# acoustic_1_0.net
KiCad netlist of a schematic drawn in EAGLE
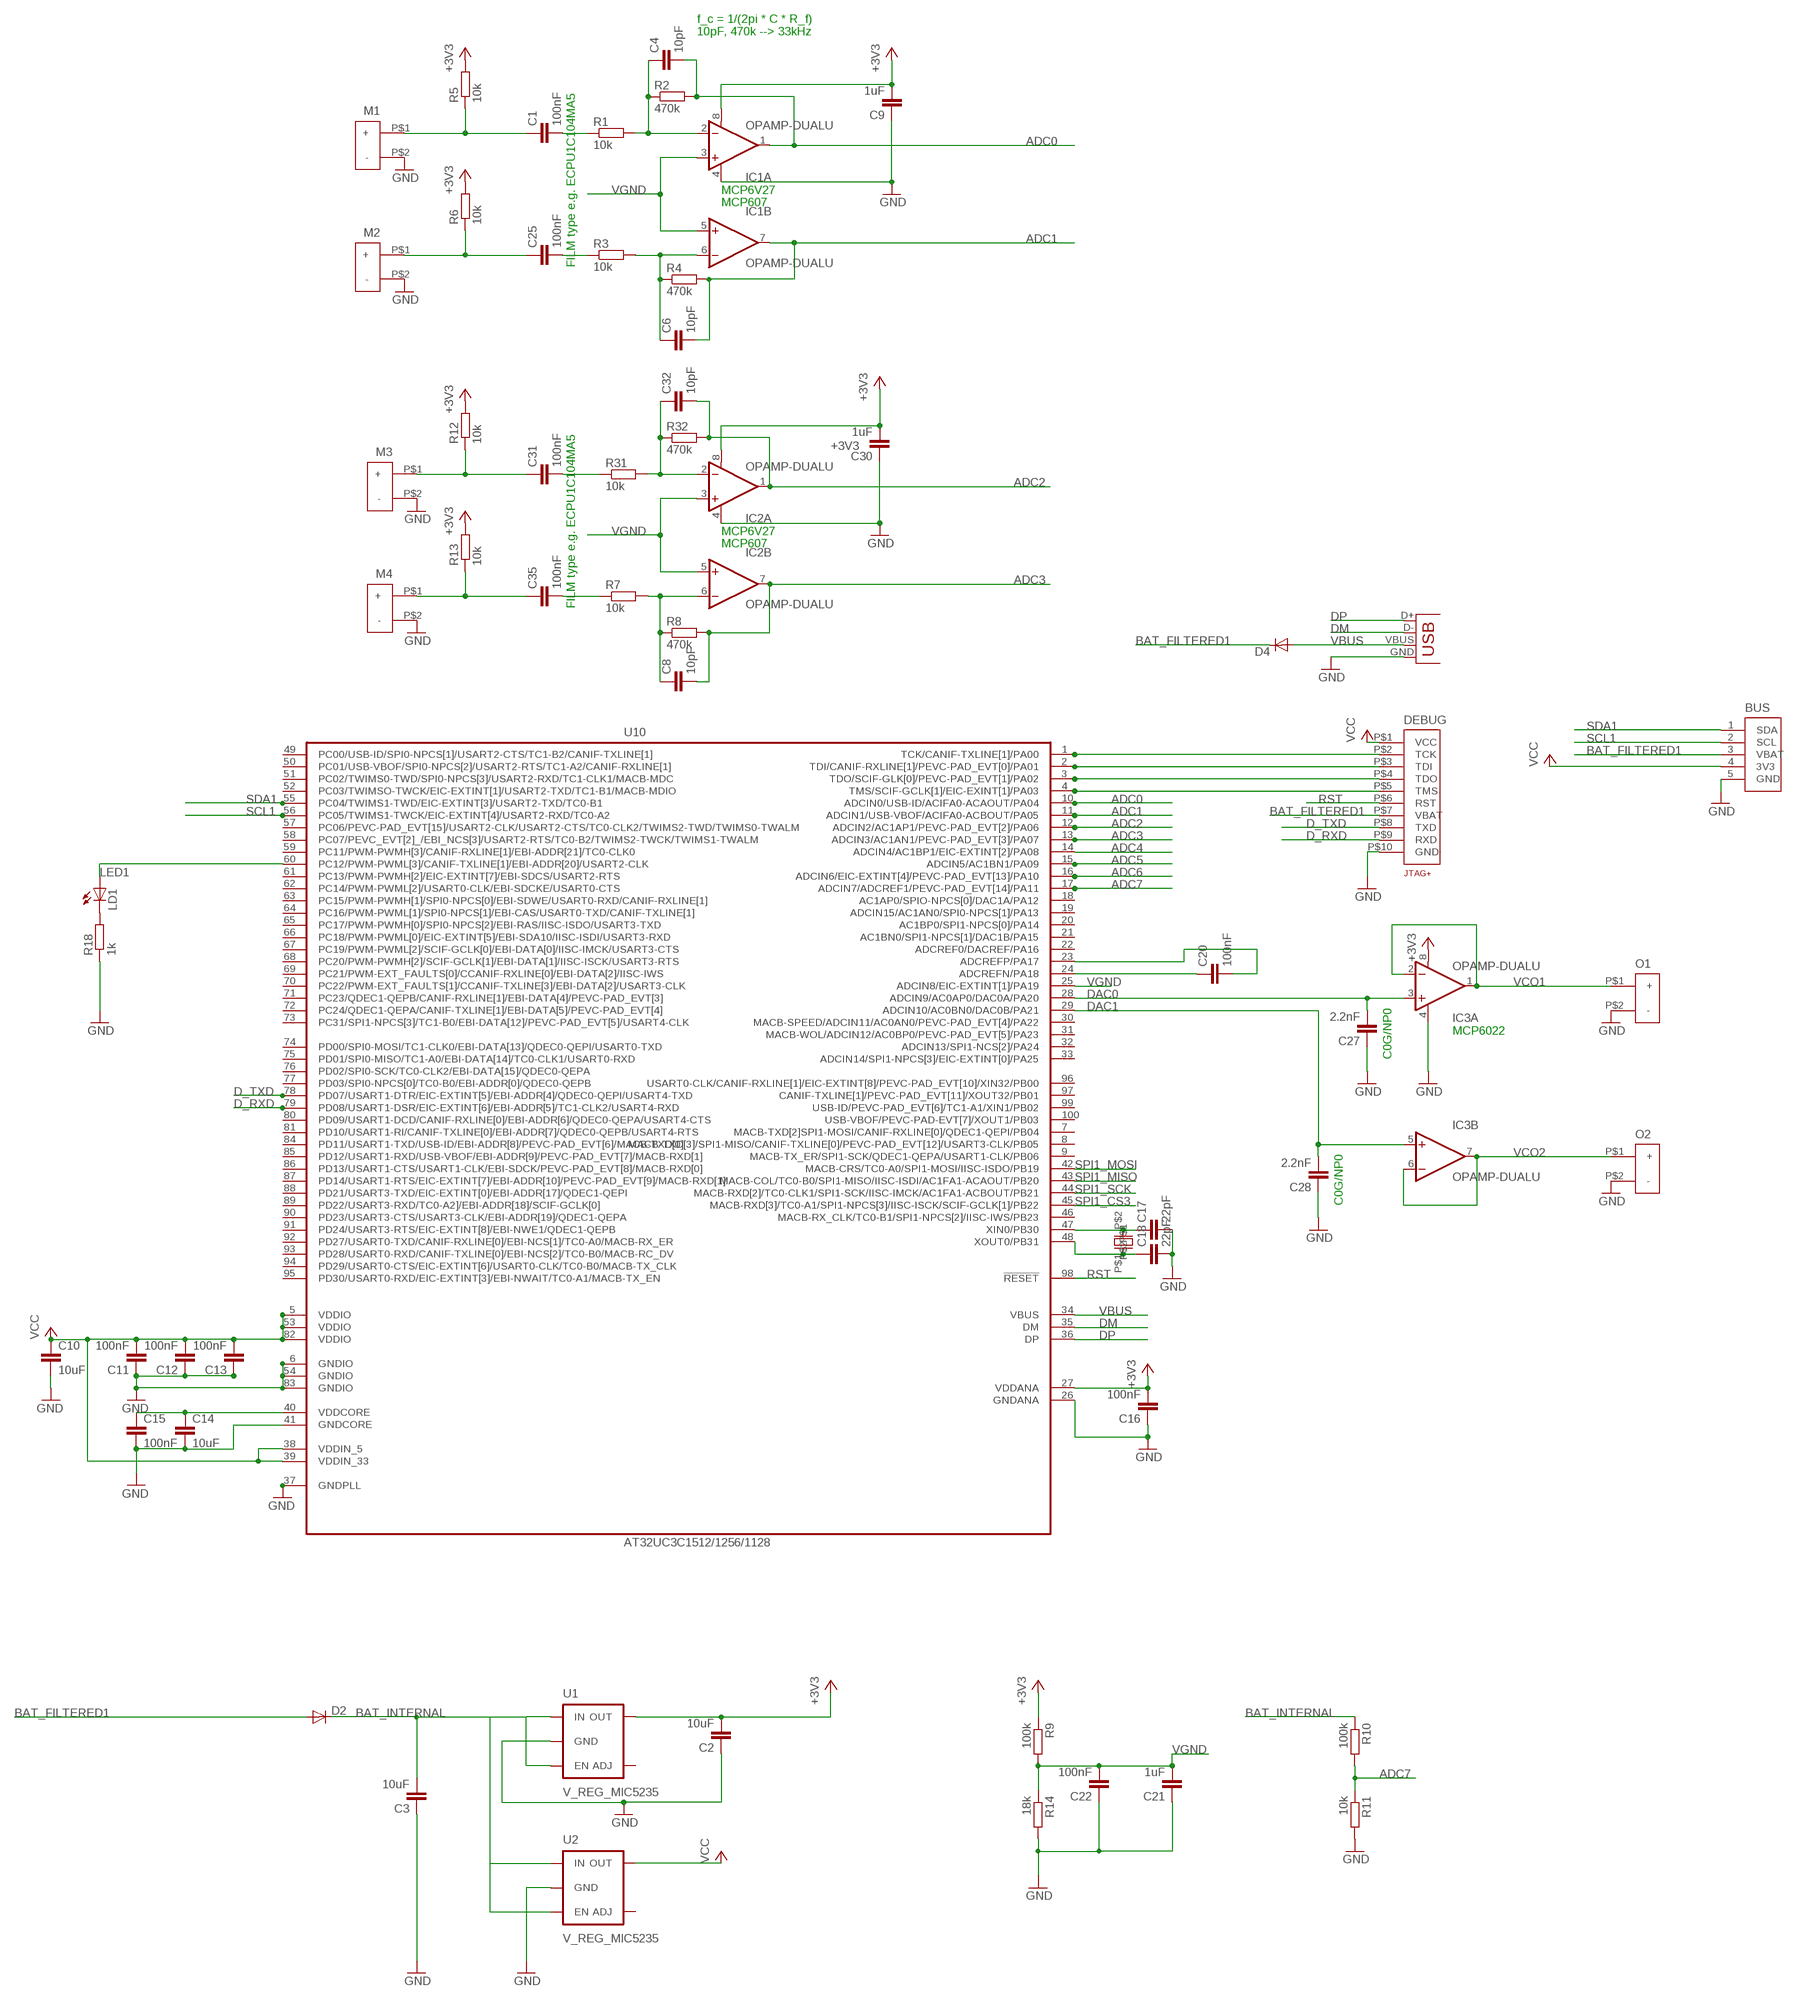
[diagram p0: schematic, sheet 1]

(export (version "E")
  (design (tool "Eeschema 10.0.6"))
  (components
    (comp (ref "BUS")
      (value "I2C_BUS_PICOVERTICAL")
      (footprint "eagle-import:MOLEX_CONNECTOR_5_PINS_VERTICAL")
      (fields (field (name "PLACE_PART") "YES"))
      (libsource (lib "eagle-import") (part "I2C_BUS_PICOVERTICAL"))
    )
    (comp (ref "C1")
      (value "100nF")
      (footprint "eagle-import:C0805")
      (libsource (lib "eagle-import") (part "C-EUC0805"))
    )
    (comp (ref "C2")
      (value "10uF")
      (footprint "eagle-import:C0805")
      (libsource (lib "eagle-import") (part "C-EUC0805"))
    )
    (comp (ref "C3")
      (value "10uF")
      (footprint "eagle-import:C0805")
      (libsource (lib "eagle-import") (part "C-EUC0805"))
    )
    (comp (ref "C4")
      (value "10pF")
      (footprint "eagle-import:C0603")
      (libsource (lib "eagle-import") (part "C-EUC0603"))
    )
    (comp (ref "C6")
      (value "10pF")
      (footprint "eagle-import:C0603")
      (libsource (lib "eagle-import") (part "C-EUC0603"))
    )
    (comp (ref "C8")
      (value "10pF")
      (footprint "eagle-import:C0603")
      (libsource (lib "eagle-import") (part "C-EUC0603"))
    )
    (comp (ref "C9")
      (value "1uF")
      (footprint "eagle-import:C0805")
      (libsource (lib "eagle-import") (part "C-EUC0805"))
    )
    (comp (ref "C10")
      (value "10uF")
      (footprint "eagle-import:C0805")
      (libsource (lib "eagle-import") (part "C-EUC0805"))
    )
    (comp (ref "C11")
      (value "100nF")
      (footprint "eagle-import:C0603")
      (libsource (lib "eagle-import") (part "C-EUC0603"))
    )
    (comp (ref "C12")
      (value "100nF")
      (footprint "eagle-import:C0603")
      (libsource (lib "eagle-import") (part "C-EUC0603"))
    )
    (comp (ref "C13")
      (value "100nF")
      (footprint "eagle-import:C0603")
      (libsource (lib "eagle-import") (part "C-EUC0603"))
    )
    (comp (ref "C14")
      (value "10uF")
      (footprint "eagle-import:C0805")
      (libsource (lib "eagle-import") (part "C-EUC0805"))
    )
    (comp (ref "C15")
      (value "100nF")
      (footprint "eagle-import:C0603")
      (libsource (lib "eagle-import") (part "C-EUC0603"))
    )
    (comp (ref "C16")
      (value "100nF")
      (footprint "eagle-import:C0603")
      (libsource (lib "eagle-import") (part "C-EUC0603"))
    )
    (comp (ref "C17")
      (value "22pF")
      (footprint "eagle-import:C0402")
      (libsource (lib "eagle-import") (part "C-EUC0402"))
    )
    (comp (ref "C18")
      (value "22pF")
      (footprint "eagle-import:C0402")
      (libsource (lib "eagle-import") (part "C-EUC0402"))
    )
    (comp (ref "C20")
      (value "100nF")
      (footprint "eagle-import:C0603")
      (libsource (lib "eagle-import") (part "C-EUC0603"))
    )
    (comp (ref "C21")
      (value "1uF")
      (footprint "eagle-import:C0805")
      (libsource (lib "eagle-import") (part "C-EUC0805"))
    )
    (comp (ref "C22")
      (value "100nF")
      (footprint "eagle-import:C0603")
      (libsource (lib "eagle-import") (part "C-EUC0603"))
    )
    (comp (ref "C25")
      (value "100nF")
      (footprint "eagle-import:C0805")
      (libsource (lib "eagle-import") (part "C-EUC0805"))
    )
    (comp (ref "C27")
      (value "2.2nF")
      (footprint "eagle-import:C0805")
      (libsource (lib "eagle-import") (part "C-EUC0805"))
    )
    (comp (ref "C28")
      (value "2.2nF")
      (footprint "eagle-import:C0805")
      (libsource (lib "eagle-import") (part "C-EUC0805"))
    )
    (comp (ref "C30")
      (value "1uF")
      (footprint "eagle-import:C0805")
      (libsource (lib "eagle-import") (part "C-EUC0805"))
    )
    (comp (ref "C31")
      (value "100nF")
      (footprint "eagle-import:C0805")
      (libsource (lib "eagle-import") (part "C-EUC0805"))
    )
    (comp (ref "C32")
      (value "10pF")
      (footprint "eagle-import:C0603")
      (libsource (lib "eagle-import") (part "C-EUC0603"))
    )
    (comp (ref "C35")
      (value "100nF")
      (footprint "eagle-import:C0805")
      (libsource (lib "eagle-import") (part "C-EUC0805"))
    )
    (comp (ref "D2")
      (value "DIODESOD")
      (footprint "eagle-import:SOD-323")
      (libsource (lib "eagle-import") (part "DIODESOD"))
    )
    (comp (ref "D4")
      (value "DIODESOD")
      (footprint "eagle-import:SOD-323")
      (libsource (lib "eagle-import") (part "DIODESOD"))
    )
    (comp (ref "DEBUG")
      (value "AVR32_JTAG+SERIALHIROSE_DF13")
      (footprint "eagle-import:MOLEX_CONNECTOR_10PINS")
      (fields (field (name "PLACE_PART") "YES"))
      (libsource (lib "eagle-import") (part "AVR32_JTAG+SERIALHIROSE_DF13"))
    )
    (comp (ref "IC1")
      (value "OPAMP-DUALU")
      (footprint "eagle-import:SO08")
      (libsource (lib "eagle-import") (part "OPAMP-DUALU"))
    )
    (comp (ref "IC2")
      (value "OPAMP-DUALU")
      (footprint "eagle-import:SO08")
      (libsource (lib "eagle-import") (part "OPAMP-DUALU"))
    )
    (comp (ref "IC3")
      (value "OPAMP-DUALU")
      (footprint "eagle-import:SO08")
      (libsource (lib "eagle-import") (part "OPAMP-DUALU"))
    )
    (comp (ref "LD1")
      (value "LEDCHIPLED_0805")
      (footprint "eagle-import:CHIPLED_0805")
      (libsource (lib "eagle-import") (part "LEDCHIPLED_0805"))
    )
    (comp (ref "M1")
      (value "POWER")
      (footprint "eagle-import:POWER")
      (fields (field (name "PLACE_PART") "YES"))
      (libsource (lib "eagle-import") (part "POWER"))
    )
    (comp (ref "M2")
      (value "POWER")
      (footprint "eagle-import:POWER")
      (fields (field (name "PLACE_PART") "YES"))
      (libsource (lib "eagle-import") (part "POWER"))
    )
    (comp (ref "M3")
      (value "POWER")
      (footprint "eagle-import:POWER")
      (fields (field (name "PLACE_PART") "YES"))
      (libsource (lib "eagle-import") (part "POWER"))
    )
    (comp (ref "M4")
      (value "POWER")
      (footprint "eagle-import:POWER")
      (fields (field (name "PLACE_PART") "YES"))
      (libsource (lib "eagle-import") (part "POWER"))
    )
    (comp (ref "O1")
      (value "POWER")
      (footprint "eagle-import:POWER")
      (fields (field (name "PLACE_PART") "YES"))
      (libsource (lib "eagle-import") (part "POWER"))
    )
    (comp (ref "O2")
      (value "POWER")
      (footprint "eagle-import:POWER")
      (fields (field (name "PLACE_PART") "YES"))
      (libsource (lib "eagle-import") (part "POWER"))
    )
    (comp (ref "R1")
      (value "10k")
      (footprint "eagle-import:R0603")
      (libsource (lib "eagle-import") (part "R-EU_R0603"))
    )
    (comp (ref "R2")
      (value "470k")
      (footprint "eagle-import:R0603")
      (libsource (lib "eagle-import") (part "R-EU_R0603"))
    )
    (comp (ref "R3")
      (value "10k")
      (footprint "eagle-import:R0603")
      (libsource (lib "eagle-import") (part "R-EU_R0603"))
    )
    (comp (ref "R4")
      (value "470k")
      (footprint "eagle-import:R0603")
      (libsource (lib "eagle-import") (part "R-EU_R0603"))
    )
    (comp (ref "R5")
      (value "10k")
      (footprint "eagle-import:R0603")
      (libsource (lib "eagle-import") (part "R-EU_R0603"))
    )
    (comp (ref "R6")
      (value "10k")
      (footprint "eagle-import:R0603")
      (libsource (lib "eagle-import") (part "R-EU_R0603"))
    )
    (comp (ref "R7")
      (value "10k")
      (footprint "eagle-import:R0603")
      (libsource (lib "eagle-import") (part "R-EU_R0603"))
    )
    (comp (ref "R8")
      (value "470k")
      (footprint "eagle-import:R0603")
      (libsource (lib "eagle-import") (part "R-EU_R0603"))
    )
    (comp (ref "R9")
      (value "100k")
      (footprint "eagle-import:R0603")
      (libsource (lib "eagle-import") (part "R-EU_R0603"))
    )
    (comp (ref "R10")
      (value "100k")
      (footprint "eagle-import:R0603")
      (libsource (lib "eagle-import") (part "R-EU_R0603"))
    )
    (comp (ref "R11")
      (value "10k")
      (footprint "eagle-import:R0603")
      (libsource (lib "eagle-import") (part "R-EU_R0603"))
    )
    (comp (ref "R12")
      (value "10k")
      (footprint "eagle-import:R0603")
      (libsource (lib "eagle-import") (part "R-EU_R0603"))
    )
    (comp (ref "R13")
      (value "10k")
      (footprint "eagle-import:R0603")
      (libsource (lib "eagle-import") (part "R-EU_R0603"))
    )
    (comp (ref "R14")
      (value "18k")
      (footprint "eagle-import:R0603")
      (libsource (lib "eagle-import") (part "R-EU_R0603"))
    )
    (comp (ref "R18")
      (value "1k")
      (footprint "eagle-import:R0603")
      (libsource (lib "eagle-import") (part "R-EU_R0603"))
    )
    (comp (ref "R31")
      (value "10k")
      (footprint "eagle-import:R0603")
      (libsource (lib "eagle-import") (part "R-EU_R0603"))
    )
    (comp (ref "R32")
      (value "470k")
      (footprint "eagle-import:R0603")
      (libsource (lib "eagle-import") (part "R-EU_R0603"))
    )
    (comp (ref "U$8")
      (value "CRYSTAL")
      (footprint "eagle-import:SMD_CRYSTAL_ABM")
      (fields (field (name "PLACE_PART") "YES"))
      (libsource (lib "eagle-import") (part "CRYSTAL"))
    )
    (comp (ref "U1")
      (value "V_REG_MIC5235")
      (footprint "eagle-import:SOT23-5")
      (libsource (lib "eagle-import") (part "V_REG_MIC5235"))
    )
    (comp (ref "U2")
      (value "V_REG_MIC5235")
      (footprint "eagle-import:SOT23-5")
      (libsource (lib "eagle-import") (part "V_REG_MIC5235"))
    )
    (comp (ref "U10")
      (value "AT32UC3C1512/1256/1128")
      (footprint "eagle-import:TQFP100")
      (fields (field (name "PLACE_PART") "YES"))
      (libsource (lib "eagle-import") (part "AT32UC3C1512/1256/1128"))
    )
    (comp (ref "X1")
      (value "USB-MICROB")
      (footprint "eagle-import:USB-MICROB")
      (libsource (lib "eagle-import") (part "USB-MICROB"))
    )
  )
  (nets
    (net (code "1") (name "+3V3") (class "Default")
      (node (ref "C16") (pin "2") (pinfunction "2_2") (pintype "passive"))
      (node (ref "C2") (pin "2") (pinfunction "2_2") (pintype "passive"))
      (node (ref "C30") (pin "2") (pinfunction "2_2") (pintype "passive"))
      (node (ref "C9") (pin "2") (pinfunction "2_2") (pintype "passive"))
      (node (ref "IC1") (pin "8") (pinfunction "V+_8") (pintype "power_in"))
      (node (ref "IC2") (pin "8") (pinfunction "V+_8") (pintype "power_in"))
      (node (ref "IC3") (pin "8") (pinfunction "V+_8") (pintype "power_in"))
      (node (ref "R12") (pin "2") (pinfunction "2_2") (pintype "passive"))
      (node (ref "R13") (pin "2") (pinfunction "2_2") (pintype "passive"))
      (node (ref "R5") (pin "2") (pinfunction "2_2") (pintype "passive"))
      (node (ref "R6") (pin "2") (pinfunction "2_2") (pintype "passive"))
      (node (ref "R9") (pin "1") (pinfunction "1_1") (pintype "passive"))
      (node (ref "U1") (pin "5") (pinfunction "OUT_5") (pintype "passive"))
      (node (ref "U10") (pin "27") (pinfunction "VDDANA_27") (pintype "power_in"))
    )
    (net (code "2") (name "/ADC0") (class "Default")
      (node (ref "C4") (pin "2") (pinfunction "2_2") (pintype "passive"))
      (node (ref "IC1") (pin "1") (pinfunction "OUT_1") (pintype "output"))
      (node (ref "R2") (pin "2") (pinfunction "2_2") (pintype "passive"))
      (node (ref "U10") (pin "10") (pinfunction "ADCIN0/USB-ID/ACIFA0-ACAOUT/PA04_10") (pintype "bidirectional"))
    )
    (net (code "3") (name "/ADC1") (class "Default")
      (node (ref "C6") (pin "2") (pinfunction "2_2") (pintype "passive"))
      (node (ref "IC1") (pin "7") (pinfunction "OUT_7") (pintype "output"))
      (node (ref "R4") (pin "2") (pinfunction "2_2") (pintype "passive"))
      (node (ref "U10") (pin "11") (pinfunction "ADCIN1/USB-VBOF/ACIFA0-ACBOUT/PA05_11") (pintype "bidirectional"))
    )
    (net (code "4") (name "/ADC2") (class "Default")
      (node (ref "C32") (pin "2") (pinfunction "2_2") (pintype "passive"))
      (node (ref "IC2") (pin "1") (pinfunction "OUT_1") (pintype "output"))
      (node (ref "R32") (pin "2") (pinfunction "2_2") (pintype "passive"))
      (node (ref "U10") (pin "12") (pinfunction "ADCIN2/AC1AP1/PEVC-PAD_EVT[2]/PA06_12") (pintype "bidirectional"))
    )
    (net (code "5") (name "/ADC3") (class "Default")
      (node (ref "C8") (pin "2") (pinfunction "2_2") (pintype "passive"))
      (node (ref "IC2") (pin "7") (pinfunction "OUT_7") (pintype "output"))
      (node (ref "R8") (pin "2") (pinfunction "2_2") (pintype "passive"))
      (node (ref "U10") (pin "13") (pinfunction "ADCIN3/AC1AN1/PEVC-PAD_EVT[3]/PA07_13") (pintype "bidirectional"))
    )
    (net (code "6") (name "/ADC4") (class "Default")
      (node (ref "U10") (pin "14") (pinfunction "ADCIN4/AC1BP1/EIC-EXTINT[2]/PA08_14") (pintype "bidirectional"))
    )
    (net (code "7") (name "/ADC5") (class "Default")
      (node (ref "U10") (pin "15") (pinfunction "ADCIN5/AC1BN1/PA09_15") (pintype "bidirectional"))
    )
    (net (code "8") (name "/ADC6") (class "Default")
      (node (ref "U10") (pin "16") (pinfunction "ADCIN6/EIC-EXTINT[4]/PEVC-PAD_EVT[13]/PA10_16") (pintype "bidirectional"))
    )
    (net (code "9") (name "/ADC7") (class "Default")
      (node (ref "R10") (pin "2") (pinfunction "2_2") (pintype "passive"))
      (node (ref "R11") (pin "1") (pinfunction "1_1") (pintype "passive"))
      (node (ref "U10") (pin "17") (pinfunction "ADCIN7/ADCREF1/PEVC-PAD_EVT[14]/PA11_17") (pintype "bidirectional"))
    )
    (net (code "10") (name "/BAT_FILTERED1") (class "Default")
      (node (ref "BUS") (pin "3") (pinfunction "VBAT_3") (pintype "bidirectional"))
      (node (ref "D2") (pin "2") (pinfunction "A_2") (pintype "passive"))
      (node (ref "D4") (pin "1") (pinfunction "C_1") (pintype "passive"))
      (node (ref "DEBUG") (pin "P$7") (pinfunction "VBAT_P$7") (pintype "bidirectional"))
    )
    (net (code "11") (name "/BAT_INTERNAL") (class "Default")
      (node (ref "C3") (pin "2") (pinfunction "2_2") (pintype "passive"))
      (node (ref "D2") (pin "1") (pinfunction "C_1") (pintype "passive"))
      (node (ref "R10") (pin "1") (pinfunction "1_1") (pintype "passive"))
      (node (ref "U1") (pin "1") (pinfunction "IN_1") (pintype "input"))
      (node (ref "U1") (pin "3") (pinfunction "EN_3") (pintype "input"))
      (node (ref "U2") (pin "1") (pinfunction "IN_1") (pintype "input"))
      (node (ref "U2") (pin "3") (pinfunction "EN_3") (pintype "input"))
    )
    (net (code "12") (name "/DAC0") (class "Default")
      (node (ref "C27") (pin "2") (pinfunction "2_2") (pintype "passive"))
      (node (ref "IC3") (pin "3") (pinfunction "+IN_3") (pintype "input"))
      (node (ref "U10") (pin "28") (pinfunction "ADCIN9/AC0AP0/DAC0A/PA20_28") (pintype "bidirectional"))
    )
    (net (code "13") (name "/DAC1") (class "Default")
      (node (ref "C28") (pin "2") (pinfunction "2_2") (pintype "passive"))
      (node (ref "IC3") (pin "5") (pinfunction "+IN_5") (pintype "input"))
      (node (ref "U10") (pin "29") (pinfunction "ADCIN10/AC0BN0/DAC0B/PA21_29") (pintype "bidirectional"))
    )
    (net (code "14") (name "/DM") (class "Default")
      (node (ref "U10") (pin "35") (pinfunction "DM_35") (pintype "bidirectional"))
      (node (ref "X1") (pin "D-") (pinfunction "D-_D-") (pintype "bidirectional"))
    )
    (net (code "15") (name "/DP") (class "Default")
      (node (ref "U10") (pin "36") (pinfunction "DP_36") (pintype "bidirectional"))
      (node (ref "X1") (pin "D+") (pinfunction "D+_D+") (pintype "bidirectional"))
    )
    (net (code "16") (name "/D_RXD") (class "Default")
      (node (ref "DEBUG") (pin "P$9") (pinfunction "RXD_P$9") (pintype "bidirectional"))
      (node (ref "U10") (pin "79") (pinfunction "PD08/USART1-DSR/EIC-EXTINT[6]/EBI-ADDR[5]/TC1-CLK2/USART4-RXD_79") (pintype "bidirectional"))
    )
    (net (code "17") (name "/D_TXD") (class "Default")
      (node (ref "DEBUG") (pin "P$8") (pinfunction "TXD_P$8") (pintype "bidirectional"))
      (node (ref "U10") (pin "78") (pinfunction "PD07/USART1-DTR/EIC-EXTINT[5]/EBI-ADDR[4]/QDEC0-QEPI/USART4-TXD_78") (pintype "bidirectional"))
    )
    (net (code "18") (name "/LED1") (class "Default")
      (node (ref "LD1") (pin "A") (pinfunction "A_A") (pintype "passive"))
      (node (ref "U10") (pin "60") (pinfunction "PC12/PWM-PWML[3]/CANIF-TXLINE[1]/EBI-ADDR[20]/USART2-CLK_60") (pintype "bidirectional"))
    )
    (net (code "19") (name "/RST") (class "Default")
      (node (ref "DEBUG") (pin "P$6") (pinfunction "RST_P$6") (pintype "bidirectional"))
      (node (ref "U10") (pin "98") (pinfunction "~{RESET}_98") (pintype "input"))
    )
    (net (code "20") (name "/SCL1") (class "Default")
      (node (ref "BUS") (pin "2") (pinfunction "SCL_2") (pintype "bidirectional"))
      (node (ref "U10") (pin "56") (pinfunction "PC05/TWIMS1-TWCK/EIC-EXTINT[4]/USART2-RXD/TC0-A2_56") (pintype "bidirectional"))
    )
    (net (code "21") (name "/SDA1") (class "Default")
      (node (ref "BUS") (pin "1") (pinfunction "SDA_1") (pintype "bidirectional"))
      (node (ref "U10") (pin "55") (pinfunction "PC04/TWIMS1-TWD/EIC-EXTINT[3]/USART2-TXD/TC0-B1_55") (pintype "bidirectional"))
    )
    (net (code "22") (name "/SPI1_CS3") (class "Default")
      (node (ref "U10") (pin "45") (pinfunction "MACB-RXD[3]/TC0-A1/SPI1-NPCS[3]/IISC-ISCK/SCIF-GCLK[1]/PB22_45") (pintype "bidirectional"))
    )
    (net (code "23") (name "/SPI1_MISO") (class "Default")
      (node (ref "U10") (pin "43") (pinfunction "MACB-COL/TC0-B0/SPI1-MISO/IISC-ISDI/AC1FA1-ACAOUT/PB20_43") (pintype "bidirectional"))
    )
    (net (code "24") (name "/SPI1_MOSI") (class "Default")
      (node (ref "U10") (pin "42") (pinfunction "MACB-CRS/TC0-A0/SPI1-MOSI/IISC-ISDO/PB19_42") (pintype "bidirectional"))
    )
    (net (code "25") (name "/SPI1_SCK") (class "Default")
      (node (ref "U10") (pin "44") (pinfunction "MACB-RXD[2]/TC0-CLK1/SPI1-SCK/IISC-IMCK/AC1FA1-ACBOUT/PB21_44") (pintype "bidirectional"))
    )
    (net (code "26") (name "/VBUS") (class "Default")
      (node (ref "D4") (pin "2") (pinfunction "A_2") (pintype "passive"))
      (node (ref "U10") (pin "34") (pinfunction "VBUS_34") (pintype "bidirectional"))
      (node (ref "X1") (pin "VBUS") (pinfunction "VBUS_VBUS") (pintype "bidirectional"))
    )
    (net (code "27") (name "/VCO1") (class "Default")
      (node (ref "IC3") (pin "1") (pinfunction "OUT_1") (pintype "output"))
      (node (ref "IC3") (pin "2") (pinfunction "-IN_2") (pintype "input"))
      (node (ref "O1") (pin "P$1") (pinfunction "+_P$1") (pintype "bidirectional"))
    )
    (net (code "28") (name "/VCO2") (class "Default")
      (node (ref "IC3") (pin "6") (pinfunction "-IN_6") (pintype "input"))
      (node (ref "IC3") (pin "7") (pinfunction "OUT_7") (pintype "output"))
      (node (ref "O2") (pin "P$1") (pinfunction "+_P$1") (pintype "bidirectional"))
    )
    (net (code "29") (name "/VGND") (class "Default")
      (node (ref "C21") (pin "2") (pinfunction "2_2") (pintype "passive"))
      (node (ref "C22") (pin "2") (pinfunction "2_2") (pintype "passive"))
      (node (ref "IC1") (pin "3") (pinfunction "+IN_3") (pintype "input"))
      (node (ref "IC1") (pin "5") (pinfunction "+IN_5") (pintype "input"))
      (node (ref "IC2") (pin "3") (pinfunction "+IN_3") (pintype "input"))
      (node (ref "IC2") (pin "5") (pinfunction "+IN_5") (pintype "input"))
      (node (ref "R14") (pin "1") (pinfunction "1_1") (pintype "passive"))
      (node (ref "R9") (pin "2") (pinfunction "2_2") (pintype "passive"))
      (node (ref "U10") (pin "25") (pinfunction "ADCIN8/EIC-EXTINT[1]/PA19_25") (pintype "bidirectional"))
    )
    (net (code "30") (name "GND") (class "Default")
      (node (ref "BUS") (pin "5") (pinfunction "GND_5") (pintype "bidirectional"))
      (node (ref "C10") (pin "2") (pinfunction "2_2") (pintype "passive"))
      (node (ref "C11") (pin "1") (pinfunction "1_1") (pintype "passive"))
      (node (ref "C12") (pin "1") (pinfunction "1_1") (pintype "passive"))
      (node (ref "C13") (pin "1") (pinfunction "1_1") (pintype "passive"))
      (node (ref "C14") (pin "2") (pinfunction "2_2") (pintype "passive"))
      (node (ref "C15") (pin "2") (pinfunction "2_2") (pintype "passive"))
      (node (ref "C16") (pin "1") (pinfunction "1_1") (pintype "passive"))
      (node (ref "C17") (pin "2") (pinfunction "2_2") (pintype "passive"))
      (node (ref "C18") (pin "2") (pinfunction "2_2") (pintype "passive"))
      (node (ref "C2") (pin "1") (pinfunction "1_1") (pintype "passive"))
      (node (ref "C21") (pin "1") (pinfunction "1_1") (pintype "passive"))
      (node (ref "C22") (pin "1") (pinfunction "1_1") (pintype "passive"))
      (node (ref "C27") (pin "1") (pinfunction "1_1") (pintype "passive"))
      (node (ref "C28") (pin "1") (pinfunction "1_1") (pintype "passive"))
      (node (ref "C3") (pin "1") (pinfunction "1_1") (pintype "passive"))
      (node (ref "C30") (pin "1") (pinfunction "1_1") (pintype "passive"))
      (node (ref "C9") (pin "1") (pinfunction "1_1") (pintype "passive"))
      (node (ref "DEBUG") (pin "P$10") (pinfunction "GND_P$10") (pintype "bidirectional"))
      (node (ref "IC1") (pin "4") (pinfunction "V-_4") (pintype "power_in"))
      (node (ref "IC2") (pin "4") (pinfunction "V-_4") (pintype "power_in"))
      (node (ref "IC3") (pin "4") (pinfunction "V-_4") (pintype "power_in"))
      (node (ref "M1") (pin "P$2") (pinfunction "-_P$2") (pintype "bidirectional"))
      (node (ref "M2") (pin "P$2") (pinfunction "-_P$2") (pintype "bidirectional"))
      (node (ref "M3") (pin "P$2") (pinfunction "-_P$2") (pintype "bidirectional"))
      (node (ref "M4") (pin "P$2") (pinfunction "-_P$2") (pintype "bidirectional"))
      (node (ref "O1") (pin "P$2") (pinfunction "-_P$2") (pintype "bidirectional"))
      (node (ref "O2") (pin "P$2") (pinfunction "-_P$2") (pintype "bidirectional"))
      (node (ref "R11") (pin "2") (pinfunction "2_2") (pintype "passive"))
      (node (ref "R14") (pin "2") (pinfunction "2_2") (pintype "passive"))
      (node (ref "R18") (pin "1") (pinfunction "1_1") (pintype "passive"))
      (node (ref "U1") (pin "2") (pinfunction "GND_2") (pintype "input"))
      (node (ref "U10") (pin "26") (pinfunction "GNDANA_26") (pintype "power_in"))
      (node (ref "U10") (pin "37") (pinfunction "GNDPLL_37") (pintype "power_in"))
      (node (ref "U10") (pin "41") (pinfunction "GNDCORE_41") (pintype "power_in"))
      (node (ref "U10") (pin "54") (pinfunction "GNDIO_54") (pintype "power_in"))
      (node (ref "U10") (pin "6") (pinfunction "GNDIO_6") (pintype "power_in"))
      (node (ref "U10") (pin "83") (pinfunction "GNDIO_83") (pintype "power_in"))
      (node (ref "U2") (pin "2") (pinfunction "GND_2") (pintype "input"))
      (node (ref "X1") (pin "GND") (pinfunction "GND_GND") (pintype "bidirectional"))
    )
    (net (code "31") (name "Net-(C1-Pad2)") (class "Default")
      (node (ref "C1") (pin "2") (pinfunction "2_2") (pintype "passive"))
      (node (ref "R1") (pin "1") (pinfunction "1_1") (pintype "passive"))
    )
    (net (code "32") (name "Net-(C25-Pad2)") (class "Default")
      (node (ref "C25") (pin "2") (pinfunction "2_2") (pintype "passive"))
      (node (ref "R3") (pin "1") (pinfunction "1_1") (pintype "passive"))
    )
    (net (code "33") (name "Net-(C31-Pad2)") (class "Default")
      (node (ref "C31") (pin "2") (pinfunction "2_2") (pintype "passive"))
      (node (ref "R31") (pin "1") (pinfunction "1_1") (pintype "passive"))
    )
    (net (code "34") (name "Net-(C35-Pad2)") (class "Default")
      (node (ref "C35") (pin "2") (pinfunction "2_2") (pintype "passive"))
      (node (ref "R7") (pin "1") (pinfunction "1_1") (pintype "passive"))
    )
    (net (code "35") (name "Net-(DEBUG-TCK)") (class "Default")
      (node (ref "DEBUG") (pin "P$2") (pinfunction "TCK_P$2") (pintype "bidirectional"))
      (node (ref "U10") (pin "1") (pinfunction "TCK/CANIF-TXLINE[1]/PA00_1") (pintype "bidirectional"))
    )
    (net (code "36") (name "Net-(DEBUG-TDI)") (class "Default")
      (node (ref "DEBUG") (pin "P$3") (pinfunction "TDI_P$3") (pintype "bidirectional"))
      (node (ref "U10") (pin "2") (pinfunction "TDI/CANIF-RXLINE[1]/PEVC-PAD_EVT[0]/PA01_2") (pintype "bidirectional"))
    )
    (net (code "37") (name "Net-(DEBUG-TDO)") (class "Default")
      (node (ref "DEBUG") (pin "P$4") (pinfunction "TDO_P$4") (pintype "bidirectional"))
      (node (ref "U10") (pin "3") (pinfunction "TDO/SCIF-GLK[0]/PEVC-PAD_EVT[1]/PA02_3") (pintype "bidirectional"))
    )
    (net (code "38") (name "Net-(DEBUG-TMS)") (class "Default")
      (node (ref "DEBUG") (pin "P$5") (pinfunction "TMS_P$5") (pintype "bidirectional"))
      (node (ref "U10") (pin "4") (pinfunction "TMS/SCIF-GCLK[1]/EIC-EXINT[1]/PA03_4") (pintype "bidirectional"))
    )
    (net (code "39") (name "Net-(IC1A--IN)") (class "Default")
      (node (ref "C4") (pin "1") (pinfunction "1_1") (pintype "passive"))
      (node (ref "IC1") (pin "2") (pinfunction "-IN_2") (pintype "input"))
      (node (ref "R1") (pin "2") (pinfunction "2_2") (pintype "passive"))
      (node (ref "R2") (pin "1") (pinfunction "1_1") (pintype "passive"))
    )
    (net (code "40") (name "Net-(IC1B--IN)") (class "Default")
      (node (ref "C6") (pin "1") (pinfunction "1_1") (pintype "passive"))
      (node (ref "IC1") (pin "6") (pinfunction "-IN_6") (pintype "input"))
      (node (ref "R3") (pin "2") (pinfunction "2_2") (pintype "passive"))
      (node (ref "R4") (pin "1") (pinfunction "1_1") (pintype "passive"))
    )
    (net (code "41") (name "Net-(IC2A--IN)") (class "Default")
      (node (ref "C32") (pin "1") (pinfunction "1_1") (pintype "passive"))
      (node (ref "IC2") (pin "2") (pinfunction "-IN_2") (pintype "input"))
      (node (ref "R31") (pin "2") (pinfunction "2_2") (pintype "passive"))
      (node (ref "R32") (pin "1") (pinfunction "1_1") (pintype "passive"))
    )
    (net (code "42") (name "Net-(IC2B--IN)") (class "Default")
      (node (ref "C8") (pin "1") (pinfunction "1_1") (pintype "passive"))
      (node (ref "IC2") (pin "6") (pinfunction "-IN_6") (pintype "input"))
      (node (ref "R7") (pin "2") (pinfunction "2_2") (pintype "passive"))
      (node (ref "R8") (pin "1") (pinfunction "1_1") (pintype "passive"))
    )
    (net (code "43") (name "Net-(LD1-PadC)") (class "Default")
      (node (ref "LD1") (pin "C") (pinfunction "C_C") (pintype "passive"))
      (node (ref "R18") (pin "2") (pinfunction "2_2") (pintype "passive"))
    )
    (net (code "44") (name "Net-(M1-+)") (class "Default")
      (node (ref "C1") (pin "1") (pinfunction "1_1") (pintype "passive"))
      (node (ref "M1") (pin "P$1") (pinfunction "+_P$1") (pintype "bidirectional"))
      (node (ref "R5") (pin "1") (pinfunction "1_1") (pintype "passive"))
    )
    (net (code "45") (name "Net-(M2-+)") (class "Default")
      (node (ref "C25") (pin "1") (pinfunction "1_1") (pintype "passive"))
      (node (ref "M2") (pin "P$1") (pinfunction "+_P$1") (pintype "bidirectional"))
      (node (ref "R6") (pin "1") (pinfunction "1_1") (pintype "passive"))
    )
    (net (code "46") (name "Net-(M3-+)") (class "Default")
      (node (ref "C31") (pin "1") (pinfunction "1_1") (pintype "passive"))
      (node (ref "M3") (pin "P$1") (pinfunction "+_P$1") (pintype "bidirectional"))
      (node (ref "R12") (pin "1") (pinfunction "1_1") (pintype "passive"))
    )
    (net (code "47") (name "Net-(M4-+)") (class "Default")
      (node (ref "C35") (pin "1") (pinfunction "1_1") (pintype "passive"))
      (node (ref "M4") (pin "P$1") (pinfunction "+_P$1") (pintype "bidirectional"))
      (node (ref "R13") (pin "1") (pinfunction "1_1") (pintype "passive"))
    )
    (net (code "48") (name "Net-(U10-ADCREFN{slash}PA18)") (class "Default")
      (node (ref "C20") (pin "1") (pinfunction "1_1") (pintype "passive"))
      (node (ref "U10") (pin "24") (pinfunction "ADCREFN/PA18_24") (pintype "bidirectional"))
    )
    (net (code "49") (name "Net-(U10-ADCREFP{slash}PA17)") (class "Default")
      (node (ref "C20") (pin "2") (pinfunction "2_2") (pintype "passive"))
      (node (ref "U10") (pin "23") (pinfunction "ADCREFP/PA17_23") (pintype "bidirectional"))
    )
    (net (code "50") (name "Net-(U10-VDDCORE)") (class "Default")
      (node (ref "C14") (pin "1") (pinfunction "1_1") (pintype "passive"))
      (node (ref "C15") (pin "1") (pinfunction "1_1") (pintype "passive"))
      (node (ref "U10") (pin "40") (pinfunction "VDDCORE_40") (pintype "power_in"))
    )
    (net (code "51") (name "Net-(U10-XIN0{slash}PB30)") (class "Default")
      (node (ref "C17") (pin "1") (pinfunction "1_1") (pintype "passive"))
      (node (ref "U$8") (pin "P$2") (pinfunction "P$2_P$2") (pintype "bidirectional"))
      (node (ref "U10") (pin "47") (pinfunction "XIN0/PB30_47") (pintype "bidirectional"))
    )
    (net (code "52") (name "Net-(U10-XOUT0{slash}PB31)") (class "Default")
      (node (ref "C18") (pin "1") (pinfunction "1_1") (pintype "passive"))
      (node (ref "U$8") (pin "P$1") (pinfunction "P$1_P$1") (pintype "bidirectional"))
      (node (ref "U10") (pin "48") (pinfunction "XOUT0/PB31_48") (pintype "bidirectional"))
    )
    (net (code "53") (name "VCC") (class "Default")
      (node (ref "BUS") (pin "4") (pinfunction "3V3_4") (pintype "bidirectional"))
      (node (ref "C10") (pin "1") (pinfunction "1_1") (pintype "passive"))
      (node (ref "C11") (pin "2") (pinfunction "2_2") (pintype "passive"))
      (node (ref "C12") (pin "2") (pinfunction "2_2") (pintype "passive"))
      (node (ref "C13") (pin "2") (pinfunction "2_2") (pintype "passive"))
      (node (ref "DEBUG") (pin "P$1") (pinfunction "VCC_P$1") (pintype "bidirectional"))
      (node (ref "U10") (pin "38") (pinfunction "VDDIN_5_38") (pintype "power_in"))
      (node (ref "U10") (pin "39") (pinfunction "VDDIN_33_39") (pintype "power_in"))
      (node (ref "U10") (pin "5") (pinfunction "VDDIO_5") (pintype "power_in"))
      (node (ref "U10") (pin "53") (pinfunction "VDDIO_53") (pintype "power_in"))
      (node (ref "U10") (pin "82") (pinfunction "VDDIO_82") (pintype "power_in"))
      (node (ref "U2") (pin "5") (pinfunction "OUT_5") (pintype "passive"))
    )
    (net (code "54") (name "unconnected-(U1-ADJ-Pad4)") (class "Default")
      (node (ref "U1") (pin "4") (pinfunction "ADJ_4") (pintype "input"))
    )
    (net (code "55") (name "unconnected-(U2-ADJ-Pad4)") (class "Default")
      (node (ref "U2") (pin "4") (pinfunction "ADJ_4") (pintype "input"))
    )
    (net (code "56") (name "unconnected-(U10-AC1AP0{slash}SPIO-NPCS[0]{slash}DAC1A{slash}PA12-Pad18)") (class "Default")
      (node (ref "U10") (pin "18") (pinfunction "AC1AP0/SPIO-NPCS[0]/DAC1A/PA12_18") (pintype "bidirectional"))
    )
    (net (code "57") (name "unconnected-(U10-AC1BN0{slash}SPI1-NPCS[1]{slash}DAC1B{slash}PA15-Pad21)") (class "Default")
      (node (ref "U10") (pin "21") (pinfunction "AC1BN0/SPI1-NPCS[1]/DAC1B/PA15_21") (pintype "bidirectional"))
    )
    (net (code "58") (name "unconnected-(U10-AC1BP0{slash}SPI1-NPCS[0]{slash}PA14-Pad20)") (class "Default")
      (node (ref "U10") (pin "20") (pinfunction "AC1BP0/SPI1-NPCS[0]/PA14_20") (pintype "bidirectional"))
    )
    (net (code "59") (name "unconnected-(U10-ADCIN13{slash}SPI1-NCS[2]{slash}PA24-Pad32)") (class "Default")
      (node (ref "U10") (pin "32") (pinfunction "ADCIN13/SPI1-NCS[2]/PA24_32") (pintype "bidirectional"))
    )
    (net (code "60") (name "unconnected-(U10-ADCIN14{slash}SPI1-NPCS[3]{slash}EIC-EXTINT[0]{slash}PA25-Pad33)") (class "Default")
      (node (ref "U10") (pin "33") (pinfunction "ADCIN14/SPI1-NPCS[3]/EIC-EXTINT[0]/PA25_33") (pintype "bidirectional"))
    )
    (net (code "61") (name "unconnected-(U10-ADCIN15{slash}AC1AN0{slash}SPI0-NPCS[1]{slash}PA13-Pad19)") (class "Default")
      (node (ref "U10") (pin "19") (pinfunction "ADCIN15/AC1AN0/SPI0-NPCS[1]/PA13_19") (pintype "bidirectional"))
    )
    (net (code "62") (name "unconnected-(U10-ADCREF0{slash}DACREF{slash}PA16-Pad22)") (class "Default")
      (node (ref "U10") (pin "22") (pinfunction "ADCREF0/DACREF/PA16_22") (pintype "bidirectional"))
    )
    (net (code "63") (name "unconnected-(U10-CANIF-TXLINE[1]{slash}PEVC-PAD_EVT[11]{slash}XOUT32{slash}PB01-Pad97)") (class "Default")
      (node (ref "U10") (pin "97") (pinfunction "CANIF-TXLINE[1]/PEVC-PAD_EVT[11]/XOUT32/PB01_97") (pintype "bidirectional"))
    )
    (net (code "64") (name "unconnected-(U10-MACB-RX_CLK{slash}TC0-B1{slash}SPI1-NPCS[2]{slash}IISC-IWS{slash}PB23-Pad46)") (class "Default")
      (node (ref "U10") (pin "46") (pinfunction "MACB-RX_CLK/TC0-B1/SPI1-NPCS[2]/IISC-IWS/PB23_46") (pintype "bidirectional"))
    )
    (net (code "65") (name "unconnected-(U10-MACB-SPEED{slash}ADCIN11{slash}AC0AN0{slash}PEVC-PAD_EVT[4]{slash}PA22-Pad30)") (class "Default")
      (node (ref "U10") (pin "30") (pinfunction "MACB-SPEED/ADCIN11/AC0AN0/PEVC-PAD_EVT[4]/PA22_30") (pintype "bidirectional"))
    )
    (net (code "66") (name "unconnected-(U10-MACB-TXD[2]SPI1-MOSI{slash}CANIF-RXLINE[0]{slash}QDEC1-QEPI{slash}PB04-Pad7)") (class "Default")
      (node (ref "U10") (pin "7") (pinfunction "MACB-TXD[2]SPI1-MOSI/CANIF-RXLINE[0]/QDEC1-QEPI/PB04_7") (pintype "bidirectional"))
    )
    (net (code "67") (name "unconnected-(U10-MACB-TXD[3]{slash}SPI1-MISO{slash}CANIF-TXLINE[0]{slash}PEVC-PAD_EVT[12]{slash}USART3-CLK{slash}PB05-Pad8)") (class "Default")
      (node (ref "U10") (pin "8") (pinfunction "MACB-TXD[3]/SPI1-MISO/CANIF-TXLINE[0]/PEVC-PAD_EVT[12]/USART3-CLK/PB05_8") (pintype "bidirectional"))
    )
    (net (code "68") (name "unconnected-(U10-MACB-TX_ER{slash}SPI1-SCK{slash}QDEC1-QEPA{slash}USART1-CLK{slash}PB06-Pad9)") (class "Default")
      (node (ref "U10") (pin "9") (pinfunction "MACB-TX_ER/SPI1-SCK/QDEC1-QEPA/USART1-CLK/PB06_9") (pintype "bidirectional"))
    )
    (net (code "69") (name "unconnected-(U10-MACB-WOL{slash}ADCIN12{slash}AC0BP0{slash}PEVC-PAD_EVT[5]{slash}PA23-Pad31)") (class "Default")
      (node (ref "U10") (pin "31") (pinfunction "MACB-WOL/ADCIN12/AC0BP0/PEVC-PAD_EVT[5]/PA23_31") (pintype "bidirectional"))
    )
    (net (code "70") (name "unconnected-(U10-PC00{slash}USB-ID{slash}SPI0-NPCS[1]{slash}USART2-CTS{slash}TC1-B2{slash}CANIF-TXLINE[1]-Pad49)") (class "Default")
      (node (ref "U10") (pin "49") (pinfunction "PC00/USB-ID/SPI0-NPCS[1]/USART2-CTS/TC1-B2/CANIF-TXLINE[1]_49") (pintype "bidirectional"))
    )
    (net (code "71") (name "unconnected-(U10-PC01{slash}USB-VBOF{slash}SPI0-NPCS[2]{slash}USART2-RTS{slash}TC1-A2{slash}CANIF-RXLINE[1]-Pad50)") (class "Default")
      (node (ref "U10") (pin "50") (pinfunction "PC01/USB-VBOF/SPI0-NPCS[2]/USART2-RTS/TC1-A2/CANIF-RXLINE[1]_50") (pintype "bidirectional"))
    )
    (net (code "72") (name "unconnected-(U10-PC02{slash}TWIMS0-TWD{slash}SPI0-NPCS[3]{slash}USART2-RXD{slash}TC1-CLK1{slash}MACB-MDC-Pad51)") (class "Default")
      (node (ref "U10") (pin "51") (pinfunction "PC02/TWIMS0-TWD/SPI0-NPCS[3]/USART2-RXD/TC1-CLK1/MACB-MDC_51") (pintype "bidirectional"))
    )
    (net (code "73") (name "unconnected-(U10-PC03{slash}TWIMSO-TWCK{slash}EIC-EXTINT[1]{slash}USART2-TXD{slash}TC1-B1{slash}MACB-MDIO-Pad52)") (class "Default")
      (node (ref "U10") (pin "52") (pinfunction "PC03/TWIMSO-TWCK/EIC-EXTINT[1]/USART2-TXD/TC1-B1/MACB-MDIO_52") (pintype "bidirectional"))
    )
    (net (code "74") (name "unconnected-(U10-PC06{slash}PEVC-PAD_EVT[15]{slash}USART2-CLK{slash}USART2-CTS{slash}TC0-CLK2{slash}TWIMS2-TWD{slash}TWIMS0-TWALM-Pad57)") (class "Default")
      (node (ref "U10") (pin "57") (pinfunction "PC06/PEVC-PAD_EVT[15]/USART2-CLK/USART2-CTS/TC0-CLK2/TWIMS2-TWD/TWIMS0-TWALM_57") (pintype "bidirectional"))
    )
    (net (code "75") (name "unconnected-(U10-PC07{slash}PEVC_EVT[2]_{slash}EBI_NCS[3]{slash}USART2-RTS{slash}TC0-B2{slash}TWIMS2-TWCK{slash}TWIMS1-TWALM-Pad58)") (class "Default")
      (node (ref "U10") (pin "58") (pinfunction "PC07/PEVC_EVT[2]_/EBI_NCS[3]/USART2-RTS/TC0-B2/TWIMS2-TWCK/TWIMS1-TWALM_58") (pintype "bidirectional"))
    )
    (net (code "76") (name "unconnected-(U10-PC11{slash}PWM-PWMH[3]{slash}CANIF-RXLINE[1]{slash}EBI-ADDR[21]{slash}TC0-CLK0-Pad59)") (class "Default")
      (node (ref "U10") (pin "59") (pinfunction "PC11/PWM-PWMH[3]/CANIF-RXLINE[1]/EBI-ADDR[21]/TC0-CLK0_59") (pintype "bidirectional"))
    )
    (net (code "77") (name "unconnected-(U10-PC13{slash}PWM-PWMH[2]{slash}EIC-EXTINT[7]{slash}EBI-SDCS{slash}USART2-RTS-Pad61)") (class "Default")
      (node (ref "U10") (pin "61") (pinfunction "PC13/PWM-PWMH[2]/EIC-EXTINT[7]/EBI-SDCS/USART2-RTS_61") (pintype "bidirectional"))
    )
    (net (code "78") (name "unconnected-(U10-PC14{slash}PWM-PWML[2]{slash}USART0-CLK{slash}EBI-SDCKE{slash}USART0-CTS-Pad62)") (class "Default")
      (node (ref "U10") (pin "62") (pinfunction "PC14/PWM-PWML[2]/USART0-CLK/EBI-SDCKE/USART0-CTS_62") (pintype "bidirectional"))
    )
    (net (code "79") (name "unconnected-(U10-PC15{slash}PWM-PWMH[1]{slash}SPI0-NPCS[0]{slash}EBI-SDWE{slash}USART0-RXD{slash}CANIF-RXLINE[1]-Pad63)") (class "Default")
      (node (ref "U10") (pin "63") (pinfunction "PC15/PWM-PWMH[1]/SPI0-NPCS[0]/EBI-SDWE/USART0-RXD/CANIF-RXLINE[1]_63") (pintype "bidirectional"))
    )
    (net (code "80") (name "unconnected-(U10-PC16{slash}PWM-PWML[1]{slash}SPI0-NPCS[1]{slash}EBI-CAS{slash}USART0-TXD{slash}CANIF-TXLINE[1]-Pad64)") (class "Default")
      (node (ref "U10") (pin "64") (pinfunction "PC16/PWM-PWML[1]/SPI0-NPCS[1]/EBI-CAS/USART0-TXD/CANIF-TXLINE[1]_64") (pintype "bidirectional"))
    )
    (net (code "81") (name "unconnected-(U10-PC17{slash}PWM-PWMH[0]{slash}SPI0-NPCS[2]{slash}EBI-RAS{slash}IISC-ISDO{slash}USART3-TXD-Pad65)") (class "Default")
      (node (ref "U10") (pin "65") (pinfunction "PC17/PWM-PWMH[0]/SPI0-NPCS[2]/EBI-RAS/IISC-ISDO/USART3-TXD_65") (pintype "bidirectional"))
    )
    (net (code "82") (name "unconnected-(U10-PC18{slash}PWM-PWML[0]{slash}EIC-EXTINT[5]{slash}EBI-SDA10{slash}IISC-ISDI{slash}USART3-RXD-Pad66)") (class "Default")
      (node (ref "U10") (pin "66") (pinfunction "PC18/PWM-PWML[0]/EIC-EXTINT[5]/EBI-SDA10/IISC-ISDI/USART3-RXD_66") (pintype "bidirectional"))
    )
    (net (code "83") (name "unconnected-(U10-PC19{slash}PWM-PWML[2]{slash}SCIF-GCLK[0]{slash}EBI-DATA[0]{slash}IISC-IMCK{slash}USART3-CTS-Pad67)") (class "Default")
      (node (ref "U10") (pin "67") (pinfunction "PC19/PWM-PWML[2]/SCIF-GCLK[0]/EBI-DATA[0]/IISC-IMCK/USART3-CTS_67") (pintype "bidirectional"))
    )
    (net (code "84") (name "unconnected-(U10-PC20{slash}PWM-PWMH[2]{slash}SCIF-GCLK[1]{slash}EBI-DATA[1]{slash}IISC-ISCK{slash}USART3-RTS-Pad68)") (class "Default")
      (node (ref "U10") (pin "68") (pinfunction "PC20/PWM-PWMH[2]/SCIF-GCLK[1]/EBI-DATA[1]/IISC-ISCK/USART3-RTS_68") (pintype "bidirectional"))
    )
    (net (code "85") (name "unconnected-(U10-PC21{slash}PWM-EXT_FAULTS[0]{slash}CCANIF-RXLINE[0]{slash}EBI-DATA[2]{slash}IISC-IWS-Pad69)") (class "Default")
      (node (ref "U10") (pin "69") (pinfunction "PC21/PWM-EXT_FAULTS[0]/CCANIF-RXLINE[0]/EBI-DATA[2]/IISC-IWS_69") (pintype "bidirectional"))
    )
    (net (code "86") (name "unconnected-(U10-PC22{slash}PWM-EXT_FAULTS[1]{slash}CCANIF-TXLINE[3]{slash}EBI-DATA[2]{slash}USART3-CLK-Pad70)") (class "Default")
      (node (ref "U10") (pin "70") (pinfunction "PC22/PWM-EXT_FAULTS[1]/CCANIF-TXLINE[3]/EBI-DATA[2]/USART3-CLK_70") (pintype "bidirectional"))
    )
    (net (code "87") (name "unconnected-(U10-PC23{slash}QDEC1-QEPB{slash}CANIF-RXLINE[1]{slash}EBI-DATA[4]{slash}PEVC-PAD_EVT[3]-Pad71)") (class "Default")
      (node (ref "U10") (pin "71") (pinfunction "PC23/QDEC1-QEPB/CANIF-RXLINE[1]/EBI-DATA[4]/PEVC-PAD_EVT[3]_71") (pintype "bidirectional"))
    )
    (net (code "88") (name "unconnected-(U10-PC24{slash}QDEC1-QEPA{slash}CANIF-TXLINE[1]{slash}EBI-DATA[5]{slash}PEVC-PAD_EVT[4]-Pad72)") (class "Default")
      (node (ref "U10") (pin "72") (pinfunction "PC24/QDEC1-QEPA/CANIF-TXLINE[1]/EBI-DATA[5]/PEVC-PAD_EVT[4]_72") (pintype "bidirectional"))
    )
    (net (code "89") (name "unconnected-(U10-PC31{slash}SPI1-NPCS[3]{slash}TC1-B0{slash}EBI-DATA[12]{slash}PEVC-PAD_EVT[5]{slash}USART4-CLK-Pad73)") (class "Default")
      (node (ref "U10") (pin "73") (pinfunction "PC31/SPI1-NPCS[3]/TC1-B0/EBI-DATA[12]/PEVC-PAD_EVT[5]/USART4-CLK_73") (pintype "bidirectional"))
    )
    (net (code "90") (name "unconnected-(U10-PD00{slash}SPI0-MOSI{slash}TC1-CLK0{slash}EBI-DATA[13]{slash}QDEC0-QEPI{slash}USART0-TXD-Pad74)") (class "Default")
      (node (ref "U10") (pin "74") (pinfunction "PD00/SPI0-MOSI/TC1-CLK0/EBI-DATA[13]/QDEC0-QEPI/USART0-TXD_74") (pintype "bidirectional"))
    )
    (net (code "91") (name "unconnected-(U10-PD01{slash}SPI0-MISO{slash}TC1-A0{slash}EBI-DATA[14]{slash}TC0-CLK1{slash}USART0-RXD-Pad75)") (class "Default")
      (node (ref "U10") (pin "75") (pinfunction "PD01/SPI0-MISO/TC1-A0/EBI-DATA[14]/TC0-CLK1/USART0-RXD_75") (pintype "bidirectional"))
    )
    (net (code "92") (name "unconnected-(U10-PD02{slash}SPI0-SCK{slash}TC0-CLK2{slash}EBI-DATA[15]{slash}QDEC0-QEPA-Pad76)") (class "Default")
      (node (ref "U10") (pin "76") (pinfunction "PD02/SPI0-SCK/TC0-CLK2/EBI-DATA[15]/QDEC0-QEPA_76") (pintype "bidirectional"))
    )
    (net (code "93") (name "unconnected-(U10-PD03{slash}SPI0-NPCS[0]{slash}TC0-B0{slash}EBI-ADDR[0]{slash}QDEC0-QEPB-Pad77)") (class "Default")
      (node (ref "U10") (pin "77") (pinfunction "PD03/SPI0-NPCS[0]/TC0-B0/EBI-ADDR[0]/QDEC0-QEPB_77") (pintype "bidirectional"))
    )
    (net (code "94") (name "unconnected-(U10-PD09{slash}USART1-DCD{slash}CANIF-RXLINE[0]{slash}EBI-ADDR[6]{slash}QDEC0-QEPA{slash}USART4-CTS-Pad80)") (class "Default")
      (node (ref "U10") (pin "80") (pinfunction "PD09/USART1-DCD/CANIF-RXLINE[0]/EBI-ADDR[6]/QDEC0-QEPA/USART4-CTS_80") (pintype "bidirectional"))
    )
    (net (code "95") (name "unconnected-(U10-PD10{slash}USART1-RI{slash}CANIF-TXLINE[0]{slash}EBI-ADDR[7]{slash}QDEC0-QEPB{slash}USART4-RTS-Pad81)") (class "Default")
      (node (ref "U10") (pin "81") (pinfunction "PD10/USART1-RI/CANIF-TXLINE[0]/EBI-ADDR[7]/QDEC0-QEPB/USART4-RTS_81") (pintype "bidirectional"))
    )
    (net (code "96") (name "unconnected-(U10-PD11{slash}USART1-TXD{slash}USB-ID{slash}EBI-ADDR[8]{slash}PEVC-PAD_EVT[6]{slash}MACB-TXD[0]-Pad84)") (class "Default")
      (node (ref "U10") (pin "84") (pinfunction "PD11/USART1-TXD/USB-ID/EBI-ADDR[8]/PEVC-PAD_EVT[6]/MACB-TXD[0]_84") (pintype "bidirectional"))
    )
    (net (code "97") (name "unconnected-(U10-PD12{slash}USART1-RXD{slash}USB-VBOF{slash}EBI-ADDR[9]{slash}PEVC-PAD_EVT[7]{slash}MACB-RXD[1]-Pad85)") (class "Default")
      (node (ref "U10") (pin "85") (pinfunction "PD12/USART1-RXD/USB-VBOF/EBI-ADDR[9]/PEVC-PAD_EVT[7]/MACB-RXD[1]_85") (pintype "bidirectional"))
    )
    (net (code "98") (name "unconnected-(U10-PD13{slash}USART1-CTS{slash}USART1-CLK{slash}EBI-SDCK{slash}PEVC-PAD_EVT[8]{slash}MACB-RXD[0]-Pad86)") (class "Default")
      (node (ref "U10") (pin "86") (pinfunction "PD13/USART1-CTS/USART1-CLK/EBI-SDCK/PEVC-PAD_EVT[8]/MACB-RXD[0]_86") (pintype "bidirectional"))
    )
    (net (code "99") (name "unconnected-(U10-PD14{slash}USART1-RTS{slash}EIC-EXTINT[7]{slash}EBI-ADDR[10]{slash}PEVC-PAD_EVT[9]{slash}MACB-RXD[1]-Pad87)") (class "Default")
      (node (ref "U10") (pin "87") (pinfunction "PD14/USART1-RTS/EIC-EXTINT[7]/EBI-ADDR[10]/PEVC-PAD_EVT[9]/MACB-RXD[1]_87") (pintype "bidirectional"))
    )
    (net (code "100") (name "unconnected-(U10-PD21{slash}USART3-TXD{slash}EIC-EXTINT[0]{slash}EBI-ADDR[17]{slash}QDEC1-QEPI-Pad88)") (class "Default")
      (node (ref "U10") (pin "88") (pinfunction "PD21/USART3-TXD/EIC-EXTINT[0]/EBI-ADDR[17]/QDEC1-QEPI_88") (pintype "bidirectional"))
    )
    (net (code "101") (name "unconnected-(U10-PD22{slash}USART3-RXD{slash}TC0-A2]{slash}EBI-ADDR[18]{slash}SCIF-GCLK[0]-Pad89)") (class "Default")
      (node (ref "U10") (pin "89") (pinfunction "PD22/USART3-RXD/TC0-A2]/EBI-ADDR[18]/SCIF-GCLK[0]_89") (pintype "bidirectional"))
    )
    (net (code "102") (name "unconnected-(U10-PD23{slash}USART3-CTS{slash}USART3-CLK{slash}EBI-ADDR[19]{slash}QDEC1-QEPA-Pad90)") (class "Default")
      (node (ref "U10") (pin "90") (pinfunction "PD23/USART3-CTS/USART3-CLK/EBI-ADDR[19]/QDEC1-QEPA_90") (pintype "bidirectional"))
    )
    (net (code "103") (name "unconnected-(U10-PD24{slash}USART3-RTS{slash}EIC-EXTINT[8]{slash}EBI-NWE1{slash}QDEC1-QEPB-Pad91)") (class "Default")
      (node (ref "U10") (pin "91") (pinfunction "PD24/USART3-RTS/EIC-EXTINT[8]/EBI-NWE1/QDEC1-QEPB_91") (pintype "bidirectional"))
    )
    (net (code "104") (name "unconnected-(U10-PD27{slash}USART0-TXD{slash}CANIF-RXLINE[0]{slash}EBI-NCS[1]{slash}TC0-A0{slash}MACB-RX_ER-Pad92)") (class "Default")
      (node (ref "U10") (pin "92") (pinfunction "PD27/USART0-TXD/CANIF-RXLINE[0]/EBI-NCS[1]/TC0-A0/MACB-RX_ER_92") (pintype "bidirectional"))
    )
    (net (code "105") (name "unconnected-(U10-PD28{slash}USART0-RXD{slash}CANIF-TXLINE[0]{slash}EBI-NCS[2]{slash}TC0-B0{slash}MACB-RC_DV-Pad93)") (class "Default")
      (node (ref "U10") (pin "93") (pinfunction "PD28/USART0-RXD/CANIF-TXLINE[0]/EBI-NCS[2]/TC0-B0/MACB-RC_DV_93") (pintype "bidirectional"))
    )
    (net (code "106") (name "unconnected-(U10-PD29{slash}USART0-CTS{slash}EIC-EXTINT[6]{slash}USART0-CLK{slash}TC0-B0{slash}MACB-TX_CLK-Pad94)") (class "Default")
      (node (ref "U10") (pin "94") (pinfunction "PD29/USART0-CTS/EIC-EXTINT[6]/USART0-CLK/TC0-B0/MACB-TX_CLK_94") (pintype "bidirectional"))
    )
    (net (code "107") (name "unconnected-(U10-PD30{slash}USART0-RXD{slash}EIC-EXTINT[3]{slash}EBI-NWAIT{slash}TC0-A1{slash}MACB-TX_EN-Pad95)") (class "Default")
      (node (ref "U10") (pin "95") (pinfunction "PD30/USART0-RXD/EIC-EXTINT[3]/EBI-NWAIT/TC0-A1/MACB-TX_EN_95") (pintype "bidirectional"))
    )
    (net (code "108") (name "unconnected-(U10-USART0-CLK{slash}CANIF-RXLINE[1]{slash}EIC-EXTINT[8]{slash}PEVC-PAD_EVT[10]{slash}XIN32{slash}PB00-Pad96)") (class "Default")
      (node (ref "U10") (pin "96") (pinfunction "USART0-CLK/CANIF-RXLINE[1]/EIC-EXTINT[8]/PEVC-PAD_EVT[10]/XIN32/PB00_96") (pintype "bidirectional"))
    )
    (net (code "109") (name "unconnected-(U10-USB-ID{slash}PEVC-PAD_EVT[6]{slash}TC1-A1{slash}XIN1{slash}PB02-Pad99)") (class "Default")
      (node (ref "U10") (pin "99") (pinfunction "USB-ID/PEVC-PAD_EVT[6]/TC1-A1/XIN1/PB02_99") (pintype "bidirectional"))
    )
    (net (code "110") (name "unconnected-(U10-USB-VBOF{slash}PEVC-PAD-EVT[7]{slash}XOUT1{slash}PB03-Pad100)") (class "Default")
      (node (ref "U10") (pin "100") (pinfunction "USB-VBOF/PEVC-PAD-EVT[7]/XOUT1/PB03_100") (pintype "bidirectional"))
    )
  )
)
